# buttonboard-right.net
KiCad netlist of a schematic drawn in EAGLE
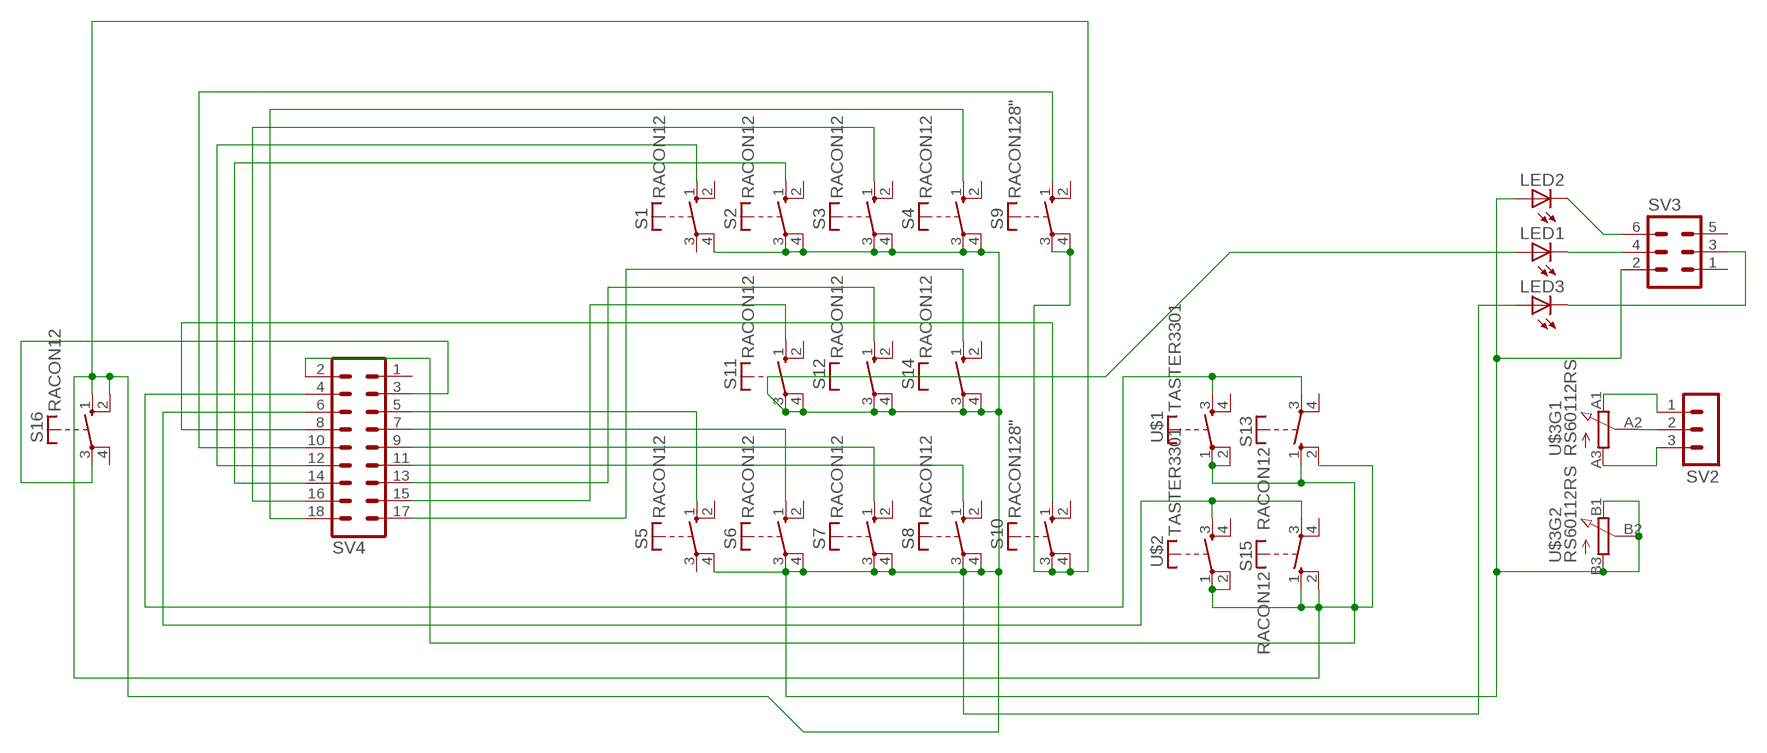
[diagram p0: schematic, sheet 1]

(export (version "E")
  (design (tool "Eeschema 10.0.6"))
  (components
    (comp (ref "LED1")
      (value "LED3MM")
      (footprint "eagle-import:LED3MM")
      (libsource (lib "eagle-import") (part "LED3MM"))
    )
    (comp (ref "LED2")
      (value "LED3MM")
      (footprint "eagle-import:LED3MM")
      (libsource (lib "eagle-import") (part "LED3MM"))
    )
    (comp (ref "LED3")
      (value "LED3MM")
      (footprint "eagle-import:LED3MM")
      (libsource (lib "eagle-import") (part "LED3MM"))
    )
    (comp (ref "S1")
      (value "RACON12")
      (footprint "eagle-import:RACON12")
      (libsource (lib "eagle-import") (part "RACON12"))
    )
    (comp (ref "S2")
      (value "RACON12")
      (footprint "eagle-import:RACON12")
      (libsource (lib "eagle-import") (part "RACON12"))
    )
    (comp (ref "S3")
      (value "RACON12")
      (footprint "eagle-import:RACON12")
      (libsource (lib "eagle-import") (part "RACON12"))
    )
    (comp (ref "S4")
      (value "RACON12")
      (footprint "eagle-import:RACON12")
      (libsource (lib "eagle-import") (part "RACON12"))
    )
    (comp (ref "S5")
      (value "RACON12")
      (footprint "eagle-import:RACON12")
      (libsource (lib "eagle-import") (part "RACON12"))
    )
    (comp (ref "S6")
      (value "RACON12")
      (footprint "eagle-import:RACON12")
      (libsource (lib "eagle-import") (part "RACON12"))
    )
    (comp (ref "S7")
      (value "RACON12")
      (footprint "eagle-import:RACON12")
      (libsource (lib "eagle-import") (part "RACON12"))
    )
    (comp (ref "S8")
      (value "RACON12")
      (footprint "eagle-import:RACON12")
      (libsource (lib "eagle-import") (part "RACON12"))
    )
    (comp (ref "S9")
      (value "RACON128\"")
      (footprint "eagle-import:RACON8")
      (libsource (lib "eagle-import") (part "RACON128{dblquote}"))
    )
    (comp (ref "S10")
      (value "RACON128\"")
      (footprint "eagle-import:RACON8")
      (libsource (lib "eagle-import") (part "RACON128{dblquote}"))
    )
    (comp (ref "S11")
      (value "RACON12")
      (footprint "eagle-import:RACON12")
      (libsource (lib "eagle-import") (part "RACON12"))
    )
    (comp (ref "S12")
      (value "RACON12")
      (footprint "eagle-import:RACON12")
      (libsource (lib "eagle-import") (part "RACON12"))
    )
    (comp (ref "S13")
      (value "RACON12")
      (footprint "eagle-import:RACON12")
      (libsource (lib "eagle-import") (part "RACON12"))
    )
    (comp (ref "S14")
      (value "RACON12")
      (footprint "eagle-import:RACON12")
      (libsource (lib "eagle-import") (part "RACON12"))
    )
    (comp (ref "S15")
      (value "RACON12")
      (footprint "eagle-import:RACON12")
      (libsource (lib "eagle-import") (part "RACON12"))
    )
    (comp (ref "S16")
      (value "RACON12")
      (footprint "eagle-import:RACON12")
      (libsource (lib "eagle-import") (part "RACON12"))
    )
    (comp (ref "SV2")
      (value "MA03-1")
      (footprint "eagle-import:MA03-1")
      (libsource (lib "eagle-import") (part "MA03-1"))
    )
    (comp (ref "SV3")
      (value "MA03-2")
      (footprint "eagle-import:MA03-2")
      (libsource (lib "eagle-import") (part "MA03-2"))
    )
    (comp (ref "SV4")
      (value "MA09-2")
      (footprint "eagle-import:MA09-2")
      (fields (field (name "OC_FARNELL") "unknown") (field (name "OC_NEWARK") "unknown"))
      (libsource (lib "eagle-import") (part "MA09-2"))
    )
    (comp (ref "U$1")
      (value "TASTER3301")
      (footprint "eagle-import:3301")
      (libsource (lib "eagle-import") (part "TASTER3301"))
    )
    (comp (ref "U$2")
      (value "TASTER3301")
      (footprint "eagle-import:3301")
      (libsource (lib "eagle-import") (part "TASTER3301"))
    )
    (comp (ref "U$3")
      (value "RS60112RS")
      (footprint "eagle-import:RS60112")
      (libsource (lib "eagle-import") (part "RS60112RS"))
    )
  )
  (nets
    (net (code "1") (name "Net-(LED1-C)") (class "Default")
      (node (ref "LED1") (pin "K") (pinfunction "C_K") (pintype "passive"))
      (node (ref "SV3") (pin "4") (pinfunction "4_4") (pintype "passive"))
    )
    (net (code "2") (name "Net-(LED2-C)") (class "Default")
      (node (ref "LED2") (pin "K") (pinfunction "C_K") (pintype "passive"))
      (node (ref "SV3") (pin "6") (pinfunction "6_6") (pintype "passive"))
    )
    (net (code "3") (name "Net-(LED3-C)") (class "Default")
      (node (ref "LED3") (pin "K") (pinfunction "C_K") (pintype "passive"))
      (node (ref "SV3") (pin "3") (pinfunction "3_3") (pintype "passive"))
    )
    (net (code "4") (name "Net-(S1-S-Pad1)") (class "Default")
      (node (ref "S1") (pin "1") (pinfunction "S_1") (pintype "passive"))
      (node (ref "SV4") (pin "12") (pinfunction "12_12") (pintype "passive"))
    )
    (net (code "5") (name "Net-(S2-S-Pad1)") (class "Default")
      (node (ref "S2") (pin "1") (pinfunction "S_1") (pintype "passive"))
      (node (ref "SV4") (pin "14") (pinfunction "14_14") (pintype "passive"))
    )
    (net (code "6") (name "Net-(S3-S-Pad1)") (class "Default")
      (node (ref "S3") (pin "1") (pinfunction "S_1") (pintype "passive"))
      (node (ref "SV4") (pin "16") (pinfunction "16_16") (pintype "passive"))
    )
    (net (code "7") (name "Net-(S4-S-Pad1)") (class "Default")
      (node (ref "S4") (pin "1") (pinfunction "S_1") (pintype "passive"))
      (node (ref "SV4") (pin "18") (pinfunction "18_18") (pintype "passive"))
    )
    (net (code "8") (name "Net-(S5-S-Pad1)") (class "Default")
      (node (ref "S5") (pin "1") (pinfunction "S_1") (pintype "passive"))
      (node (ref "SV4") (pin "5") (pinfunction "5_5") (pintype "passive"))
    )
    (net (code "9") (name "Net-(S6-S-Pad1)") (class "Default")
      (node (ref "S6") (pin "1") (pinfunction "S_1") (pintype "passive"))
      (node (ref "SV4") (pin "7") (pinfunction "7_7") (pintype "passive"))
    )
    (net (code "10") (name "Net-(S7-S-Pad1)") (class "Default")
      (node (ref "S7") (pin "1") (pinfunction "S_1") (pintype "passive"))
      (node (ref "SV4") (pin "9") (pinfunction "9_9") (pintype "passive"))
    )
    (net (code "11") (name "Net-(S8-S-Pad1)") (class "Default")
      (node (ref "S8") (pin "1") (pinfunction "S_1") (pintype "passive"))
      (node (ref "SV4") (pin "11") (pinfunction "11_11") (pintype "passive"))
    )
    (net (code "12") (name "Net-(S9-S-Pad1)") (class "Default")
      (node (ref "S9") (pin "1") (pinfunction "S_1") (pintype "passive"))
      (node (ref "SV4") (pin "10") (pinfunction "10_10") (pintype "passive"))
    )
    (net (code "13") (name "Net-(S10-S-Pad1)") (class "Default")
      (node (ref "S10") (pin "1") (pinfunction "S_1") (pintype "passive"))
      (node (ref "SV4") (pin "8") (pinfunction "8_8") (pintype "passive"))
    )
    (net (code "14") (name "Net-(S11-S-Pad1)") (class "Default")
      (node (ref "S11") (pin "1") (pinfunction "S_1") (pintype "passive"))
      (node (ref "SV4") (pin "15") (pinfunction "15_15") (pintype "passive"))
    )
    (net (code "15") (name "Net-(S12-S-Pad1)") (class "Default")
      (node (ref "S12") (pin "1") (pinfunction "S_1") (pintype "passive"))
      (node (ref "SV4") (pin "13") (pinfunction "13_13") (pintype "passive"))
    )
    (net (code "16") (name "Net-(S13-P-Pad3)") (class "Default")
      (node (ref "S13") (pin "3") (pinfunction "P_3") (pintype "passive"))
      (node (ref "SV4") (pin "4") (pinfunction "4_4") (pintype "passive"))
      (node (ref "U$1") (pin "3") (pinfunction "S_3") (pintype "passive"))
    )
    (net (code "17") (name "Net-(S14-S-Pad1)") (class "Default")
      (node (ref "S14") (pin "1") (pinfunction "S_1") (pintype "passive"))
      (node (ref "SV4") (pin "17") (pinfunction "17_17") (pintype "passive"))
    )
    (net (code "18") (name "Net-(S15-P-Pad3)") (class "Default")
      (node (ref "S15") (pin "3") (pinfunction "P_3") (pintype "passive"))
      (node (ref "SV4") (pin "6") (pinfunction "6_6") (pintype "passive"))
      (node (ref "U$2") (pin "3") (pinfunction "S_3") (pintype "passive"))
    )
    (net (code "19") (name "Net-(S16-P-Pad3)") (class "Default")
      (node (ref "S16") (pin "3") (pinfunction "P_3") (pintype "passive"))
      (node (ref "SV4") (pin "3") (pinfunction "3_3") (pintype "passive"))
    )
    (net (code "20") (name "Net-(U$3A-A)") (class "Default")
      (node (ref "SV2") (pin "3") (pinfunction "3_3") (pintype "passive"))
      (node (ref "U$3") (pin "A3") (pinfunction "A_A3") (pintype "passive"))
    )
    (net (code "21") (name "Net-(U$3A-E)") (class "Default")
      (node (ref "SV2") (pin "1") (pinfunction "1_1") (pintype "passive"))
      (node (ref "U$3") (pin "A1") (pinfunction "E_A1") (pintype "passive"))
    )
    (net (code "22") (name "Net-(U$3A-S)") (class "Default")
      (node (ref "SV2") (pin "2") (pinfunction "2_2") (pintype "passive"))
      (node (ref "U$3") (pin "A2") (pinfunction "S_A2") (pintype "passive"))
    )
    (net (code "23") (name "Net-(U$3B-A)") (class "Default")
      (node (ref "LED1") (pin "A") (pinfunction "A_A") (pintype "passive"))
      (node (ref "LED2") (pin "A") (pinfunction "A_A") (pintype "passive"))
      (node (ref "LED3") (pin "A") (pinfunction "A_A") (pintype "passive"))
      (node (ref "S1") (pin "4") (pinfunction "P_4") (pintype "passive"))
      (node (ref "S10") (pin "3") (pinfunction "P_3") (pintype "passive"))
      (node (ref "S10") (pin "4") (pinfunction "P_4") (pintype "passive"))
      (node (ref "S11") (pin "3") (pinfunction "P_3") (pintype "passive"))
      (node (ref "S11") (pin "4") (pinfunction "P_4") (pintype "passive"))
      (node (ref "S12") (pin "3") (pinfunction "P_3") (pintype "passive"))
      (node (ref "S12") (pin "4") (pinfunction "P_4") (pintype "passive"))
      (node (ref "S13") (pin "1") (pinfunction "S_1") (pintype "passive"))
      (node (ref "S13") (pin "2") (pinfunction "S_2") (pintype "passive"))
      (node (ref "S14") (pin "3") (pinfunction "P_3") (pintype "passive"))
      (node (ref "S14") (pin "4") (pinfunction "P_4") (pintype "passive"))
      (node (ref "S15") (pin "1") (pinfunction "S_1") (pintype "passive"))
      (node (ref "S15") (pin "2") (pinfunction "S_2") (pintype "passive"))
      (node (ref "S16") (pin "1") (pinfunction "S_1") (pintype "passive"))
      (node (ref "S16") (pin "2") (pinfunction "S_2") (pintype "passive"))
      (node (ref "S2") (pin "3") (pinfunction "P_3") (pintype "passive"))
      (node (ref "S2") (pin "4") (pinfunction "P_4") (pintype "passive"))
      (node (ref "S3") (pin "3") (pinfunction "P_3") (pintype "passive"))
      (node (ref "S3") (pin "4") (pinfunction "P_4") (pintype "passive"))
      (node (ref "S4") (pin "3") (pinfunction "P_3") (pintype "passive"))
      (node (ref "S4") (pin "4") (pinfunction "P_4") (pintype "passive"))
      (node (ref "S5") (pin "4") (pinfunction "P_4") (pintype "passive"))
      (node (ref "S6") (pin "3") (pinfunction "P_3") (pintype "passive"))
      (node (ref "S6") (pin "4") (pinfunction "P_4") (pintype "passive"))
      (node (ref "S7") (pin "3") (pinfunction "P_3") (pintype "passive"))
      (node (ref "S7") (pin "4") (pinfunction "P_4") (pintype "passive"))
      (node (ref "S8") (pin "3") (pinfunction "P_3") (pintype "passive"))
      (node (ref "S8") (pin "4") (pinfunction "P_4") (pintype "passive"))
      (node (ref "S9") (pin "3") (pinfunction "P_3") (pintype "passive"))
      (node (ref "S9") (pin "4") (pinfunction "P_4") (pintype "passive"))
      (node (ref "SV3") (pin "2") (pinfunction "2_2") (pintype "passive"))
      (node (ref "SV4") (pin "2") (pinfunction "2_2") (pintype "passive"))
      (node (ref "U$1") (pin "1") (pinfunction "P_1") (pintype "passive"))
      (node (ref "U$1") (pin "2") (pinfunction "P_2") (pintype "passive"))
      (node (ref "U$2") (pin "1") (pinfunction "P_1") (pintype "passive"))
      (node (ref "U$2") (pin "2") (pinfunction "P_2") (pintype "passive"))
      (node (ref "U$3") (pin "B1") (pinfunction "E_B1") (pintype "passive"))
      (node (ref "U$3") (pin "B2") (pinfunction "S_B2") (pintype "passive"))
      (node (ref "U$3") (pin "B3") (pinfunction "A_B3") (pintype "passive"))
    )
    (net (code "24") (name "unconnected-(S1-P-Pad3)") (class "Default")
      (node (ref "S1") (pin "3") (pinfunction "P_3") (pintype "passive"))
    )
    (net (code "25") (name "unconnected-(S1-S-Pad2)") (class "Default")
      (node (ref "S1") (pin "2") (pinfunction "S_2") (pintype "passive"))
    )
    (net (code "26") (name "unconnected-(S2-S-Pad2)") (class "Default")
      (node (ref "S2") (pin "2") (pinfunction "S_2") (pintype "passive"))
    )
    (net (code "27") (name "unconnected-(S3-S-Pad2)") (class "Default")
      (node (ref "S3") (pin "2") (pinfunction "S_2") (pintype "passive"))
    )
    (net (code "28") (name "unconnected-(S4-S-Pad2)") (class "Default")
      (node (ref "S4") (pin "2") (pinfunction "S_2") (pintype "passive"))
    )
    (net (code "29") (name "unconnected-(S5-P-Pad3)") (class "Default")
      (node (ref "S5") (pin "3") (pinfunction "P_3") (pintype "passive"))
    )
    (net (code "30") (name "unconnected-(S5-S-Pad2)") (class "Default")
      (node (ref "S5") (pin "2") (pinfunction "S_2") (pintype "passive"))
    )
    (net (code "31") (name "unconnected-(S6-S-Pad2)") (class "Default")
      (node (ref "S6") (pin "2") (pinfunction "S_2") (pintype "passive"))
    )
    (net (code "32") (name "unconnected-(S7-S-Pad2)") (class "Default")
      (node (ref "S7") (pin "2") (pinfunction "S_2") (pintype "passive"))
    )
    (net (code "33") (name "unconnected-(S8-S-Pad2)") (class "Default")
      (node (ref "S8") (pin "2") (pinfunction "S_2") (pintype "passive"))
    )
    (net (code "34") (name "unconnected-(S9-S-Pad2)") (class "Default")
      (node (ref "S9") (pin "2") (pinfunction "S_2") (pintype "passive"))
    )
    (net (code "35") (name "unconnected-(S10-S-Pad2)") (class "Default")
      (node (ref "S10") (pin "2") (pinfunction "S_2") (pintype "passive"))
    )
    (net (code "36") (name "unconnected-(S11-S-Pad2)") (class "Default")
      (node (ref "S11") (pin "2") (pinfunction "S_2") (pintype "passive"))
    )
    (net (code "37") (name "unconnected-(S12-S-Pad2)") (class "Default")
      (node (ref "S12") (pin "2") (pinfunction "S_2") (pintype "passive"))
    )
    (net (code "38") (name "unconnected-(S13-P-Pad4)") (class "Default")
      (node (ref "S13") (pin "4") (pinfunction "P_4") (pintype "passive"))
    )
    (net (code "39") (name "unconnected-(S14-S-Pad2)") (class "Default")
      (node (ref "S14") (pin "2") (pinfunction "S_2") (pintype "passive"))
    )
    (net (code "40") (name "unconnected-(S15-P-Pad4)") (class "Default")
      (node (ref "S15") (pin "4") (pinfunction "P_4") (pintype "passive"))
    )
    (net (code "41") (name "unconnected-(S16-P-Pad4)") (class "Default")
      (node (ref "S16") (pin "4") (pinfunction "P_4") (pintype "passive"))
    )
    (net (code "42") (name "unconnected-(SV3-Pad1)") (class "Default")
      (node (ref "SV3") (pin "1") (pinfunction "1_1") (pintype "passive"))
    )
    (net (code "43") (name "unconnected-(SV3-Pad5)") (class "Default")
      (node (ref "SV3") (pin "5") (pinfunction "5_5") (pintype "passive"))
    )
    (net (code "44") (name "unconnected-(SV4-Pad1)") (class "Default")
      (node (ref "SV4") (pin "1") (pinfunction "1_1") (pintype "passive"))
    )
    (net (code "45") (name "unconnected-(U$1-S-Pad4)") (class "Default")
      (node (ref "U$1") (pin "4") (pinfunction "S_4") (pintype "passive"))
    )
    (net (code "46") (name "unconnected-(U$2-S-Pad4)") (class "Default")
      (node (ref "U$2") (pin "4") (pinfunction "S_4") (pintype "passive"))
    )
  )
)
